# ADC_ADS4128.net
KiCad netlist of a schematic drawn in Altium Designer
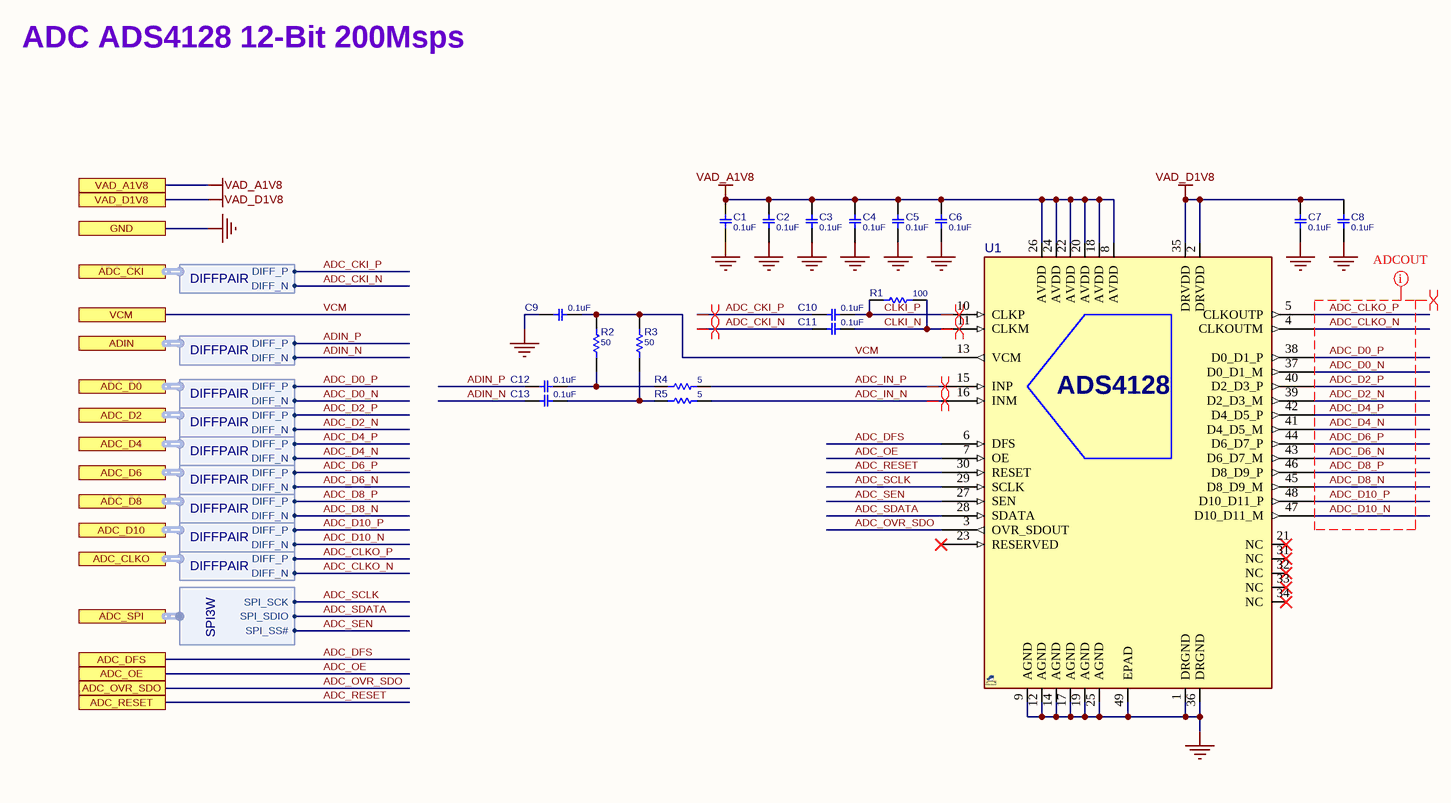
[diagram p0: ADC_ADS4128.SchDoc]

(export (version "E")
  (design (tool "Eeschema 10.0.6"))
  (components
    (comp (ref "C1")
      (value "0.1uF")
      (footprint "C0402")
      (description "CAP, MLCC")
      (libsource (lib "mlcc_smd_passive") (part "CAP_SMD_MLCC_100n50T"))
    )
    (comp (ref "C2")
      (value "0.1uF")
      (footprint "C0402")
      (description "CAP, MLCC")
      (libsource (lib "mlcc_smd_passive") (part "CAP_SMD_MLCC_100n50T"))
    )
    (comp (ref "C3")
      (value "0.1uF")
      (footprint "C0402")
      (description "CAP, MLCC")
      (libsource (lib "mlcc_smd_passive") (part "CAP_SMD_MLCC_100n50T"))
    )
    (comp (ref "C4")
      (value "0.1uF")
      (footprint "C0402")
      (description "CAP, MLCC")
      (libsource (lib "mlcc_smd_passive") (part "CAP_SMD_MLCC_100n50T"))
    )
    (comp (ref "C5")
      (value "0.1uF")
      (footprint "C0402")
      (description "CAP, MLCC")
      (libsource (lib "mlcc_smd_passive") (part "CAP_SMD_MLCC_100n50T"))
    )
    (comp (ref "C6")
      (value "0.1uF")
      (footprint "C0402")
      (description "CAP, MLCC")
      (libsource (lib "mlcc_smd_passive") (part "CAP_SMD_MLCC_100n50T"))
    )
    (comp (ref "C7")
      (value "0.1uF")
      (footprint "C0402")
      (description "CAP, MLCC")
      (libsource (lib "mlcc_smd_passive") (part "CAP_SMD_MLCC_100n50T"))
    )
    (comp (ref "C8")
      (value "0.1uF")
      (footprint "C0402")
      (description "CAP, MLCC")
      (libsource (lib "mlcc_smd_passive") (part "CAP_SMD_MLCC_100n50T"))
    )
    (comp (ref "C9")
      (value "0.1uF")
      (footprint "C0402")
      (description "CAP, MLCC")
      (libsource (lib "mlcc_smd_passive") (part "CAP_SMD_MLCC_100n50T"))
    )
    (comp (ref "C10")
      (value "0.1uF")
      (footprint "C0402")
      (description "CAP, MLCC")
      (libsource (lib "mlcc_smd_passive") (part "CAP_SMD_MLCC_100n50T"))
    )
    (comp (ref "C11")
      (value "0.1uF")
      (footprint "C0402")
      (description "CAP, MLCC")
      (libsource (lib "mlcc_smd_passive") (part "CAP_SMD_MLCC_100n50T"))
    )
    (comp (ref "C12")
      (value "0.1uF")
      (footprint "C0402")
      (description "CAP, MLCC")
      (libsource (lib "mlcc_smd_passive") (part "CAP_SMD_MLCC_100n50T"))
    )
    (comp (ref "C13")
      (value "0.1uF")
      (footprint "C0402")
      (description "CAP, MLCC")
      (libsource (lib "mlcc_smd_passive") (part "CAP_SMD_MLCC_100n50T"))
    )
    (comp (ref "R1")
      (value "100")
      (footprint "R0402")
      (description "RESISTOR, SMD")
      (fields (field (name "MANF") "Yageo"))
      (libsource (lib "passive_res_smd") (part "RES_SMD_10K_0402"))
    )
    (comp (ref "R2")
      (value "50")
      (footprint "R0402")
      (description "RESISTOR, SMD")
      (fields (field (name "MANF") "Yageo"))
      (libsource (lib "passive_res_smd") (part "RES_SMD_10K_0402"))
    )
    (comp (ref "R3")
      (value "50")
      (footprint "R0402")
      (description "RESISTOR, SMD")
      (fields (field (name "MANF") "Yageo"))
      (libsource (lib "passive_res_smd") (part "RES_SMD_10K_0402"))
    )
    (comp (ref "R4")
      (value "5")
      (footprint "R0402")
      (description "RESISTOR, SMD")
      (fields (field (name "MANF") "Yageo"))
      (libsource (lib "passive_res_smd") (part "RES_SMD_10K_0402"))
    )
    (comp (ref "R5")
      (value "5")
      (footprint "R0402")
      (description "RESISTOR, SMD")
      (fields (field (name "MANF") "Yageo"))
      (libsource (lib "passive_res_smd") (part "RES_SMD_10K_0402"))
    )
    (comp (ref "U1")
      (value "ADS4128")
      (footprint "QFN50_48T")
      (description "ADC, 12-Bit, 200MSPS, Parallel LVDS, 1.8V, QFN-48")
      (fields (field (name "MANF_P#") "ADS4128IRGZ") (field (name "MANF") "TI"))
      (libsource (lib "adc_highspeed") (part "ADS4128_QFN48"))
    )
  )
  (nets
    (net (code "4") (name "/ADC_CKI_N") (class "Default")
      (node (ref "C11") (pin "2") (pinfunction "2_2") (pintype "passive"))
    )
    (net (code "5") (name "/ADC_CKI_P") (class "Default")
      (node (ref "C10") (pin "2") (pinfunction "2_2") (pintype "passive"))
    )
    (net (code "6") (name "/ADC_CLKO_N") (class "Default")
      (node (ref "U1") (pin "4") (pinfunction "CLKOUTM_4") (pintype "output"))
    )
    (net (code "7") (name "/ADC_CLKO_P") (class "Default")
      (node (ref "U1") (pin "5") (pinfunction "CLKOUTP_5") (pintype "output"))
    )
    (net (code "8") (name "/ADC_D0_N") (class "Default")
      (node (ref "U1") (pin "37") (pinfunction "D0_D1_M_37") (pintype "output"))
    )
    (net (code "9") (name "/ADC_D0_P") (class "Default")
      (node (ref "U1") (pin "38") (pinfunction "D0_D1_P_38") (pintype "output"))
    )
    (net (code "11") (name "/ADC_D2_N") (class "Default")
      (node (ref "U1") (pin "39") (pinfunction "D2_D3_M_39") (pintype "output"))
    )
    (net (code "12") (name "/ADC_D2_P") (class "Default")
      (node (ref "U1") (pin "40") (pinfunction "D2_D3_P_40") (pintype "output"))
    )
    (net (code "13") (name "/ADC_D4_N") (class "Default")
      (node (ref "U1") (pin "41") (pinfunction "D4_D5_M_41") (pintype "output"))
    )
    (net (code "14") (name "/ADC_D4_P") (class "Default")
      (node (ref "U1") (pin "42") (pinfunction "D4_D5_P_42") (pintype "output"))
    )
    (net (code "15") (name "/ADC_D6_N") (class "Default")
      (node (ref "U1") (pin "43") (pinfunction "D6_D7_M_43") (pintype "output"))
    )
    (net (code "16") (name "/ADC_D6_P") (class "Default")
      (node (ref "U1") (pin "44") (pinfunction "D6_D7_P_44") (pintype "output"))
    )
    (net (code "17") (name "/ADC_D8_N") (class "Default")
      (node (ref "U1") (pin "45") (pinfunction "D8_D9_M_45") (pintype "output"))
    )
    (net (code "18") (name "/ADC_D8_P") (class "Default")
      (node (ref "U1") (pin "46") (pinfunction "D8_D9_P_46") (pintype "output"))
    )
    (net (code "19") (name "/ADC_D10_N") (class "Default")
      (node (ref "U1") (pin "47") (pinfunction "D10_D11_M_47") (pintype "output"))
    )
    (net (code "20") (name "/ADC_D10_P") (class "Default")
      (node (ref "U1") (pin "48") (pinfunction "D10_D11_P_48") (pintype "output"))
    )
    (net (code "21") (name "/ADC_DFS") (class "Default")
      (node (ref "U1") (pin "6") (pinfunction "DFS_6") (pintype "input"))
    )
    (net (code "22") (name "/ADC_IN_N") (class "Default")
      (node (ref "R5") (pin "2") (pinfunction "2_2") (pintype "passive"))
      (node (ref "U1") (pin "16") (pinfunction "INM_16") (pintype "input"))
    )
    (net (code "23") (name "/ADC_IN_P") (class "Default")
      (node (ref "R4") (pin "2") (pinfunction "2_2") (pintype "passive"))
      (node (ref "U1") (pin "15") (pinfunction "INP_15") (pintype "input"))
    )
    (net (code "24") (name "/ADC_OE") (class "Default")
      (node (ref "U1") (pin "7") (pinfunction "OE_7") (pintype "input"))
    )
    (net (code "25") (name "/ADC_OVR_SDO") (class "Default")
      (node (ref "U1") (pin "3") (pinfunction "OVR_SDOUT_3") (pintype "output"))
    )
    (net (code "26") (name "/ADC_RESET") (class "Default")
      (node (ref "U1") (pin "30") (pinfunction "RESET_30") (pintype "input"))
    )
    (net (code "27") (name "/ADC_SCLK") (class "Default")
      (node (ref "U1") (pin "29") (pinfunction "SCLK_29") (pintype "input"))
    )
    (net (code "28") (name "/ADC_SDATA") (class "Default")
      (node (ref "U1") (pin "28") (pinfunction "SDATA_28") (pintype "input"))
    )
    (net (code "29") (name "/ADC_SEN") (class "Default")
      (node (ref "U1") (pin "27") (pinfunction "SEN_27") (pintype "input"))
    )
    (net (code "30") (name "/ADIN_N") (class "Default")
      (node (ref "C13") (pin "2") (pinfunction "2_2") (pintype "passive"))
    )
    (net (code "31") (name "/ADIN_P") (class "Default")
      (node (ref "C12") (pin "2") (pinfunction "2_2") (pintype "passive"))
    )
    (net (code "32") (name "/CLKI_N") (class "Default")
      (node (ref "C11") (pin "1") (pinfunction "1_1") (pintype "passive"))
      (node (ref "R1") (pin "2") (pinfunction "2_2") (pintype "passive"))
      (node (ref "U1") (pin "11") (pinfunction "CLKM_11") (pintype "input"))
    )
    (net (code "33") (name "/CLKI_P") (class "Default")
      (node (ref "C10") (pin "1") (pinfunction "1_1") (pintype "passive"))
      (node (ref "R1") (pin "1") (pinfunction "1_1") (pintype "passive"))
      (node (ref "U1") (pin "10") (pinfunction "CLKP_10") (pintype "input"))
    )
    (net (code "34") (name "/VCM") (class "Default")
      (node (ref "C9") (pin "1") (pinfunction "1_1") (pintype "passive"))
      (node (ref "R2") (pin "2") (pinfunction "2_2") (pintype "passive"))
      (node (ref "R3") (pin "2") (pinfunction "2_2") (pintype "passive"))
      (node (ref "U1") (pin "13") (pinfunction "VCM_13") (pintype "output"))
    )
    (net (code "37") (name "GND") (class "Default")
      (node (ref "C1") (pin "2") (pinfunction "2_2") (pintype "passive"))
      (node (ref "C2") (pin "2") (pinfunction "2_2") (pintype "passive"))
      (node (ref "C3") (pin "2") (pinfunction "2_2") (pintype "passive"))
      (node (ref "C4") (pin "2") (pinfunction "2_2") (pintype "passive"))
      (node (ref "C5") (pin "2") (pinfunction "2_2") (pintype "passive"))
      (node (ref "C6") (pin "2") (pinfunction "2_2") (pintype "passive"))
      (node (ref "C7") (pin "2") (pinfunction "2_2") (pintype "passive"))
      (node (ref "C8") (pin "2") (pinfunction "2_2") (pintype "passive"))
      (node (ref "C9") (pin "2") (pinfunction "2_2") (pintype "passive"))
      (node (ref "U1") (pin "1") (pinfunction "DRGND_1") (pintype "power_in"))
      (node (ref "U1") (pin "12") (pinfunction "AGND_12") (pintype "power_in"))
      (node (ref "U1") (pin "14") (pinfunction "AGND_14") (pintype "power_in"))
      (node (ref "U1") (pin "17") (pinfunction "AGND_17") (pintype "power_in"))
      (node (ref "U1") (pin "19") (pinfunction "AGND_19") (pintype "power_in"))
      (node (ref "U1") (pin "25") (pinfunction "AGND_25") (pintype "power_in"))
      (node (ref "U1") (pin "36") (pinfunction "DRGND_36") (pintype "power_in"))
      (node (ref "U1") (pin "49") (pinfunction "EPAD_49") (pintype "passive"))
      (node (ref "U1") (pin "9") (pinfunction "AGND_9") (pintype "power_in"))
    )
    (net (code "38") (name "Net-(C12-Pad1)") (class "Default")
      (node (ref "C12") (pin "1") (pinfunction "1_1") (pintype "passive"))
      (node (ref "R2") (pin "1") (pinfunction "1_1") (pintype "passive"))
      (node (ref "R4") (pin "1") (pinfunction "1_1") (pintype "passive"))
    )
    (net (code "39") (name "Net-(C13-Pad1)") (class "Default")
      (node (ref "C13") (pin "1") (pinfunction "1_1") (pintype "passive"))
      (node (ref "R3") (pin "1") (pinfunction "1_1") (pintype "passive"))
      (node (ref "R5") (pin "1") (pinfunction "1_1") (pintype "passive"))
    )
    (net (code "40") (name "VAD_A1V8") (class "Default")
      (node (ref "C1") (pin "1") (pinfunction "1_1") (pintype "passive"))
      (node (ref "C2") (pin "1") (pinfunction "1_1") (pintype "passive"))
      (node (ref "C3") (pin "1") (pinfunction "1_1") (pintype "passive"))
      (node (ref "C4") (pin "1") (pinfunction "1_1") (pintype "passive"))
      (node (ref "C5") (pin "1") (pinfunction "1_1") (pintype "passive"))
      (node (ref "C6") (pin "1") (pinfunction "1_1") (pintype "passive"))
      (node (ref "U1") (pin "18") (pinfunction "AVDD_18") (pintype "power_in"))
      (node (ref "U1") (pin "20") (pinfunction "AVDD_20") (pintype "power_in"))
      (node (ref "U1") (pin "22") (pinfunction "AVDD_22") (pintype "power_in"))
      (node (ref "U1") (pin "24") (pinfunction "AVDD_24") (pintype "power_in"))
      (node (ref "U1") (pin "26") (pinfunction "AVDD_26") (pintype "power_in"))
      (node (ref "U1") (pin "8") (pinfunction "AVDD_8") (pintype "power_in"))
    )
    (net (code "41") (name "VAD_D1V8") (class "Default")
      (node (ref "C7") (pin "1") (pinfunction "1_1") (pintype "passive"))
      (node (ref "C8") (pin "1") (pinfunction "1_1") (pintype "passive"))
      (node (ref "U1") (pin "2") (pinfunction "DRVDD_2") (pintype "power_in"))
      (node (ref "U1") (pin "35") (pinfunction "DRVDD_35") (pintype "power_in"))
    )
    (net (code "42") (name "unconnected-(U1-NC-Pad21)") (class "Default")
      (node (ref "U1") (pin "21") (pinfunction "NC_21") (pintype "passive+no_connect"))
    )
    (net (code "43") (name "unconnected-(U1-NC-Pad31)") (class "Default")
      (node (ref "U1") (pin "31") (pinfunction "NC_31") (pintype "passive+no_connect"))
    )
    (net (code "44") (name "unconnected-(U1-NC-Pad32)") (class "Default")
      (node (ref "U1") (pin "32") (pinfunction "NC_32") (pintype "passive+no_connect"))
    )
    (net (code "45") (name "unconnected-(U1-NC-Pad33)") (class "Default")
      (node (ref "U1") (pin "33") (pinfunction "NC_33") (pintype "passive+no_connect"))
    )
    (net (code "46") (name "unconnected-(U1-NC-Pad34)") (class "Default")
      (node (ref "U1") (pin "34") (pinfunction "NC_34") (pintype "passive+no_connect"))
    )
    (net (code "47") (name "unconnected-(U1-RESERVED-Pad23)") (class "Default")
      (node (ref "U1") (pin "23") (pinfunction "RESERVED_23") (pintype "input+no_connect"))
    )
  )
)
